# S03-LEDS.net
KiCad netlist of a schematic drawn in Altium Designer
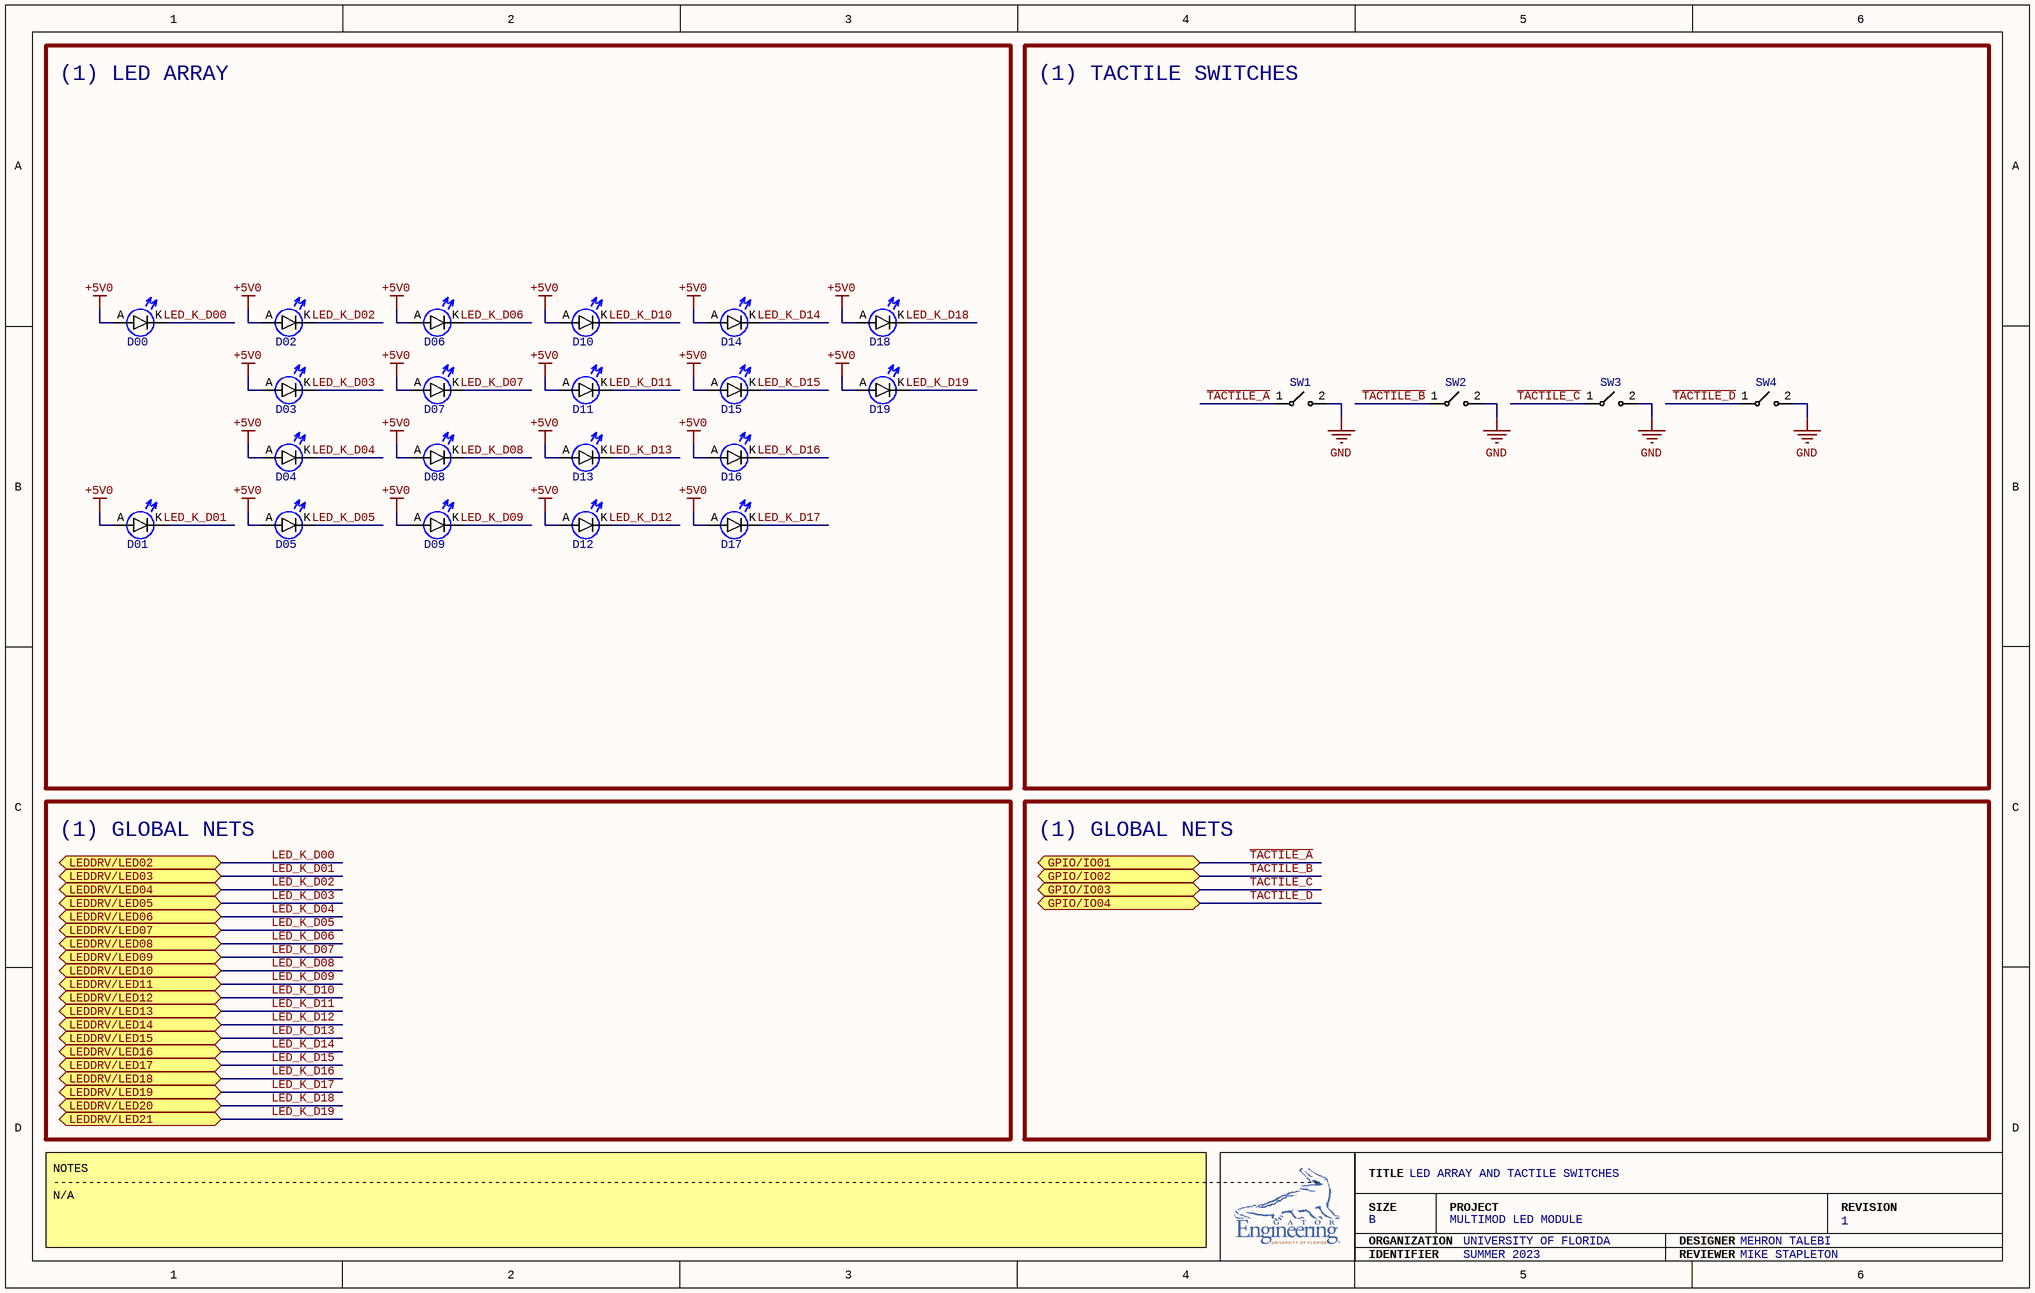
[diagram p0: S03-LEDS.SchDoc]

(export (version "E")
  (design (tool "Eeschema 10.0.6"))
  (components
    (comp (ref "D00")
      (value "XZFBB45S-9")
      (footprint "XZFBB45S-9")
      (description "LED BLUE CLEAR 2PLCC SMD")
      (libsource (lib "Master") (part "XZFBB45S-9"))
    )
    (comp (ref "D01")
      (value "XZFBB45S-9")
      (footprint "XZFBB45S-9")
      (description "LED BLUE CLEAR 2PLCC SMD")
      (libsource (lib "Master") (part "XZFBB45S-9"))
    )
    (comp (ref "D02")
      (value "XZFBB45S-9")
      (footprint "XZFBB45S-9")
      (description "LED BLUE CLEAR 2PLCC SMD")
      (libsource (lib "Master") (part "XZFBB45S-9"))
    )
    (comp (ref "D03")
      (value "XZFBB45S-9")
      (footprint "XZFBB45S-9")
      (description "LED BLUE CLEAR 2PLCC SMD")
      (libsource (lib "Master") (part "XZFBB45S-9"))
    )
    (comp (ref "D04")
      (value "XZFBB45S-9")
      (footprint "XZFBB45S-9")
      (description "LED BLUE CLEAR 2PLCC SMD")
      (libsource (lib "Master") (part "XZFBB45S-9"))
    )
    (comp (ref "D05")
      (value "XZFBB45S-9")
      (footprint "XZFBB45S-9")
      (description "LED BLUE CLEAR 2PLCC SMD")
      (libsource (lib "Master") (part "XZFBB45S-9"))
    )
    (comp (ref "D06")
      (value "XZFBB45S-9")
      (footprint "XZFBB45S-9")
      (description "LED BLUE CLEAR 2PLCC SMD")
      (libsource (lib "Master") (part "XZFBB45S-9"))
    )
    (comp (ref "D07")
      (value "XZFBB45S-9")
      (footprint "XZFBB45S-9")
      (description "LED BLUE CLEAR 2PLCC SMD")
      (libsource (lib "Master") (part "XZFBB45S-9"))
    )
    (comp (ref "D08")
      (value "XZFBB45S-9")
      (footprint "XZFBB45S-9")
      (description "LED BLUE CLEAR 2PLCC SMD")
      (libsource (lib "Master") (part "XZFBB45S-9"))
    )
    (comp (ref "D09")
      (value "XZFBB45S-9")
      (footprint "XZFBB45S-9")
      (description "LED BLUE CLEAR 2PLCC SMD")
      (libsource (lib "Master") (part "XZFBB45S-9"))
    )
    (comp (ref "D10")
      (value "XZFBB45S-9")
      (footprint "XZFBB45S-9")
      (description "LED BLUE CLEAR 2PLCC SMD")
      (libsource (lib "Master") (part "XZFBB45S-9"))
    )
    (comp (ref "D11")
      (value "XZFBB45S-9")
      (footprint "XZFBB45S-9")
      (description "LED BLUE CLEAR 2PLCC SMD")
      (libsource (lib "Master") (part "XZFBB45S-9"))
    )
    (comp (ref "D12")
      (value "XZFBB45S-9")
      (footprint "XZFBB45S-9")
      (description "LED BLUE CLEAR 2PLCC SMD")
      (libsource (lib "Master") (part "XZFBB45S-9"))
    )
    (comp (ref "D13")
      (value "XZFBB45S-9")
      (footprint "XZFBB45S-9")
      (description "LED BLUE CLEAR 2PLCC SMD")
      (libsource (lib "Master") (part "XZFBB45S-9"))
    )
    (comp (ref "D14")
      (value "XZFBB45S-9")
      (footprint "XZFBB45S-9")
      (description "LED BLUE CLEAR 2PLCC SMD")
      (libsource (lib "Master") (part "XZFBB45S-9"))
    )
    (comp (ref "D15")
      (value "XZFBB45S-9")
      (footprint "XZFBB45S-9")
      (description "LED BLUE CLEAR 2PLCC SMD")
      (libsource (lib "Master") (part "XZFBB45S-9"))
    )
    (comp (ref "D16")
      (value "XZFBB45S-9")
      (footprint "XZFBB45S-9")
      (description "LED BLUE CLEAR 2PLCC SMD")
      (libsource (lib "Master") (part "XZFBB45S-9"))
    )
    (comp (ref "D17")
      (value "XZFBB45S-9")
      (footprint "XZFBB45S-9")
      (description "LED BLUE CLEAR 2PLCC SMD")
      (libsource (lib "Master") (part "XZFBB45S-9"))
    )
    (comp (ref "D18")
      (value "XZFBB45S-9")
      (footprint "XZFBB45S-9")
      (description "LED BLUE CLEAR 2PLCC SMD")
      (libsource (lib "Master") (part "XZFBB45S-9"))
    )
    (comp (ref "D19")
      (value "XZFBB45S-9")
      (footprint "XZFBB45S-9")
      (description "LED BLUE CLEAR 2PLCC SMD")
      (libsource (lib "Master") (part "XZFBB45S-9"))
    )
    (comp (ref "SW1")
      (value "TL9210AF260Q")
      (footprint "TL9210AF260Q")
      (description "SWITCH TACTILE SPST-NO 0.05A 12V")
      (libsource (lib "Master") (part "TL9210AF260Q"))
    )
    (comp (ref "SW2")
      (value "TL9210AF260Q")
      (footprint "TL9210AF260Q")
      (description "SWITCH TACTILE SPST-NO 0.05A 12V")
      (libsource (lib "Master") (part "TL9210AF260Q"))
    )
    (comp (ref "SW3")
      (value "TL9210AF260Q")
      (footprint "TL9210AF260Q")
      (description "SWITCH TACTILE SPST-NO 0.05A 12V")
      (libsource (lib "Master") (part "TL9210AF260Q"))
    )
    (comp (ref "SW4")
      (value "TL9210AF260Q")
      (footprint "TL9210AF260Q")
      (description "SWITCH TACTILE SPST-NO 0.05A 12V")
      (libsource (lib "Master") (part "TL9210AF260Q"))
    )
  )
  (nets
    (net (code "1") (name "+5V0") (class "Default")
      (node (ref "D00") (pin "A") (pinfunction "A_A") (pintype "passive"))
      (node (ref "D01") (pin "A") (pinfunction "A_A") (pintype "passive"))
      (node (ref "D02") (pin "A") (pinfunction "A_A") (pintype "passive"))
      (node (ref "D03") (pin "A") (pinfunction "A_A") (pintype "passive"))
      (node (ref "D04") (pin "A") (pinfunction "A_A") (pintype "passive"))
      (node (ref "D05") (pin "A") (pinfunction "A_A") (pintype "passive"))
      (node (ref "D06") (pin "A") (pinfunction "A_A") (pintype "passive"))
      (node (ref "D07") (pin "A") (pinfunction "A_A") (pintype "passive"))
      (node (ref "D08") (pin "A") (pinfunction "A_A") (pintype "passive"))
      (node (ref "D09") (pin "A") (pinfunction "A_A") (pintype "passive"))
      (node (ref "D10") (pin "A") (pinfunction "A_A") (pintype "passive"))
      (node (ref "D11") (pin "A") (pinfunction "A_A") (pintype "passive"))
      (node (ref "D12") (pin "A") (pinfunction "A_A") (pintype "passive"))
      (node (ref "D13") (pin "A") (pinfunction "A_A") (pintype "passive"))
      (node (ref "D14") (pin "A") (pinfunction "A_A") (pintype "passive"))
      (node (ref "D15") (pin "A") (pinfunction "A_A") (pintype "passive"))
      (node (ref "D16") (pin "A") (pinfunction "A_A") (pintype "passive"))
      (node (ref "D17") (pin "A") (pinfunction "A_A") (pintype "passive"))
      (node (ref "D18") (pin "A") (pinfunction "A_A") (pintype "passive"))
      (node (ref "D19") (pin "A") (pinfunction "A_A") (pintype "passive"))
    )
    (net (code "2") (name "/LED_K_D00") (class "Default")
      (node (ref "D00") (pin "K") (pinfunction "K_K") (pintype "passive"))
    )
    (net (code "3") (name "/LED_K_D01") (class "Default")
      (node (ref "D01") (pin "K") (pinfunction "K_K") (pintype "passive"))
    )
    (net (code "4") (name "/LED_K_D02") (class "Default")
      (node (ref "D02") (pin "K") (pinfunction "K_K") (pintype "passive"))
    )
    (net (code "5") (name "/LED_K_D03") (class "Default")
      (node (ref "D03") (pin "K") (pinfunction "K_K") (pintype "passive"))
    )
    (net (code "6") (name "/LED_K_D04") (class "Default")
      (node (ref "D04") (pin "K") (pinfunction "K_K") (pintype "passive"))
    )
    (net (code "7") (name "/LED_K_D05") (class "Default")
      (node (ref "D05") (pin "K") (pinfunction "K_K") (pintype "passive"))
    )
    (net (code "8") (name "/LED_K_D06") (class "Default")
      (node (ref "D06") (pin "K") (pinfunction "K_K") (pintype "passive"))
    )
    (net (code "9") (name "/LED_K_D07") (class "Default")
      (node (ref "D07") (pin "K") (pinfunction "K_K") (pintype "passive"))
    )
    (net (code "10") (name "/LED_K_D08") (class "Default")
      (node (ref "D08") (pin "K") (pinfunction "K_K") (pintype "passive"))
    )
    (net (code "11") (name "/LED_K_D09") (class "Default")
      (node (ref "D09") (pin "K") (pinfunction "K_K") (pintype "passive"))
    )
    (net (code "12") (name "/LED_K_D10") (class "Default")
      (node (ref "D10") (pin "K") (pinfunction "K_K") (pintype "passive"))
    )
    (net (code "13") (name "/LED_K_D11") (class "Default")
      (node (ref "D11") (pin "K") (pinfunction "K_K") (pintype "passive"))
    )
    (net (code "14") (name "/LED_K_D12") (class "Default")
      (node (ref "D12") (pin "K") (pinfunction "K_K") (pintype "passive"))
    )
    (net (code "15") (name "/LED_K_D13") (class "Default")
      (node (ref "D13") (pin "K") (pinfunction "K_K") (pintype "passive"))
    )
    (net (code "16") (name "/LED_K_D14") (class "Default")
      (node (ref "D14") (pin "K") (pinfunction "K_K") (pintype "passive"))
    )
    (net (code "17") (name "/LED_K_D15") (class "Default")
      (node (ref "D15") (pin "K") (pinfunction "K_K") (pintype "passive"))
    )
    (net (code "18") (name "/LED_K_D16") (class "Default")
      (node (ref "D16") (pin "K") (pinfunction "K_K") (pintype "passive"))
    )
    (net (code "19") (name "/LED_K_D17") (class "Default")
      (node (ref "D17") (pin "K") (pinfunction "K_K") (pintype "passive"))
    )
    (net (code "20") (name "/LED_K_D18") (class "Default")
      (node (ref "D18") (pin "K") (pinfunction "K_K") (pintype "passive"))
    )
    (net (code "21") (name "/LED_K_D19") (class "Default")
      (node (ref "D19") (pin "K") (pinfunction "K_K") (pintype "passive"))
    )
    (net (code "22") (name "/TACTILE_A") (class "Default")
      (node (ref "SW1") (pin "1") (pinfunction "1_1") (pintype "passive"))
    )
    (net (code "23") (name "/TACTILE_B") (class "Default")
      (node (ref "SW2") (pin "1") (pinfunction "1_1") (pintype "passive"))
    )
    (net (code "24") (name "/TACTILE_C") (class "Default")
      (node (ref "SW3") (pin "1") (pinfunction "1_1") (pintype "passive"))
    )
    (net (code "25") (name "/TACTILE_D") (class "Default")
      (node (ref "SW4") (pin "1") (pinfunction "1_1") (pintype "passive"))
    )
    (net (code "26") (name "GND") (class "Default")
      (node (ref "SW1") (pin "2") (pinfunction "2_2") (pintype "passive"))
      (node (ref "SW2") (pin "2") (pinfunction "2_2") (pintype "passive"))
      (node (ref "SW3") (pin "2") (pinfunction "2_2") (pintype "passive"))
      (node (ref "SW4") (pin "2") (pinfunction "2_2") (pintype "passive"))
    )
  )
)
